# 08_-_POWER_CONTROL_AND_DISTRIBUTION.net
KiCad netlist of a schematic drawn in Altium Designer
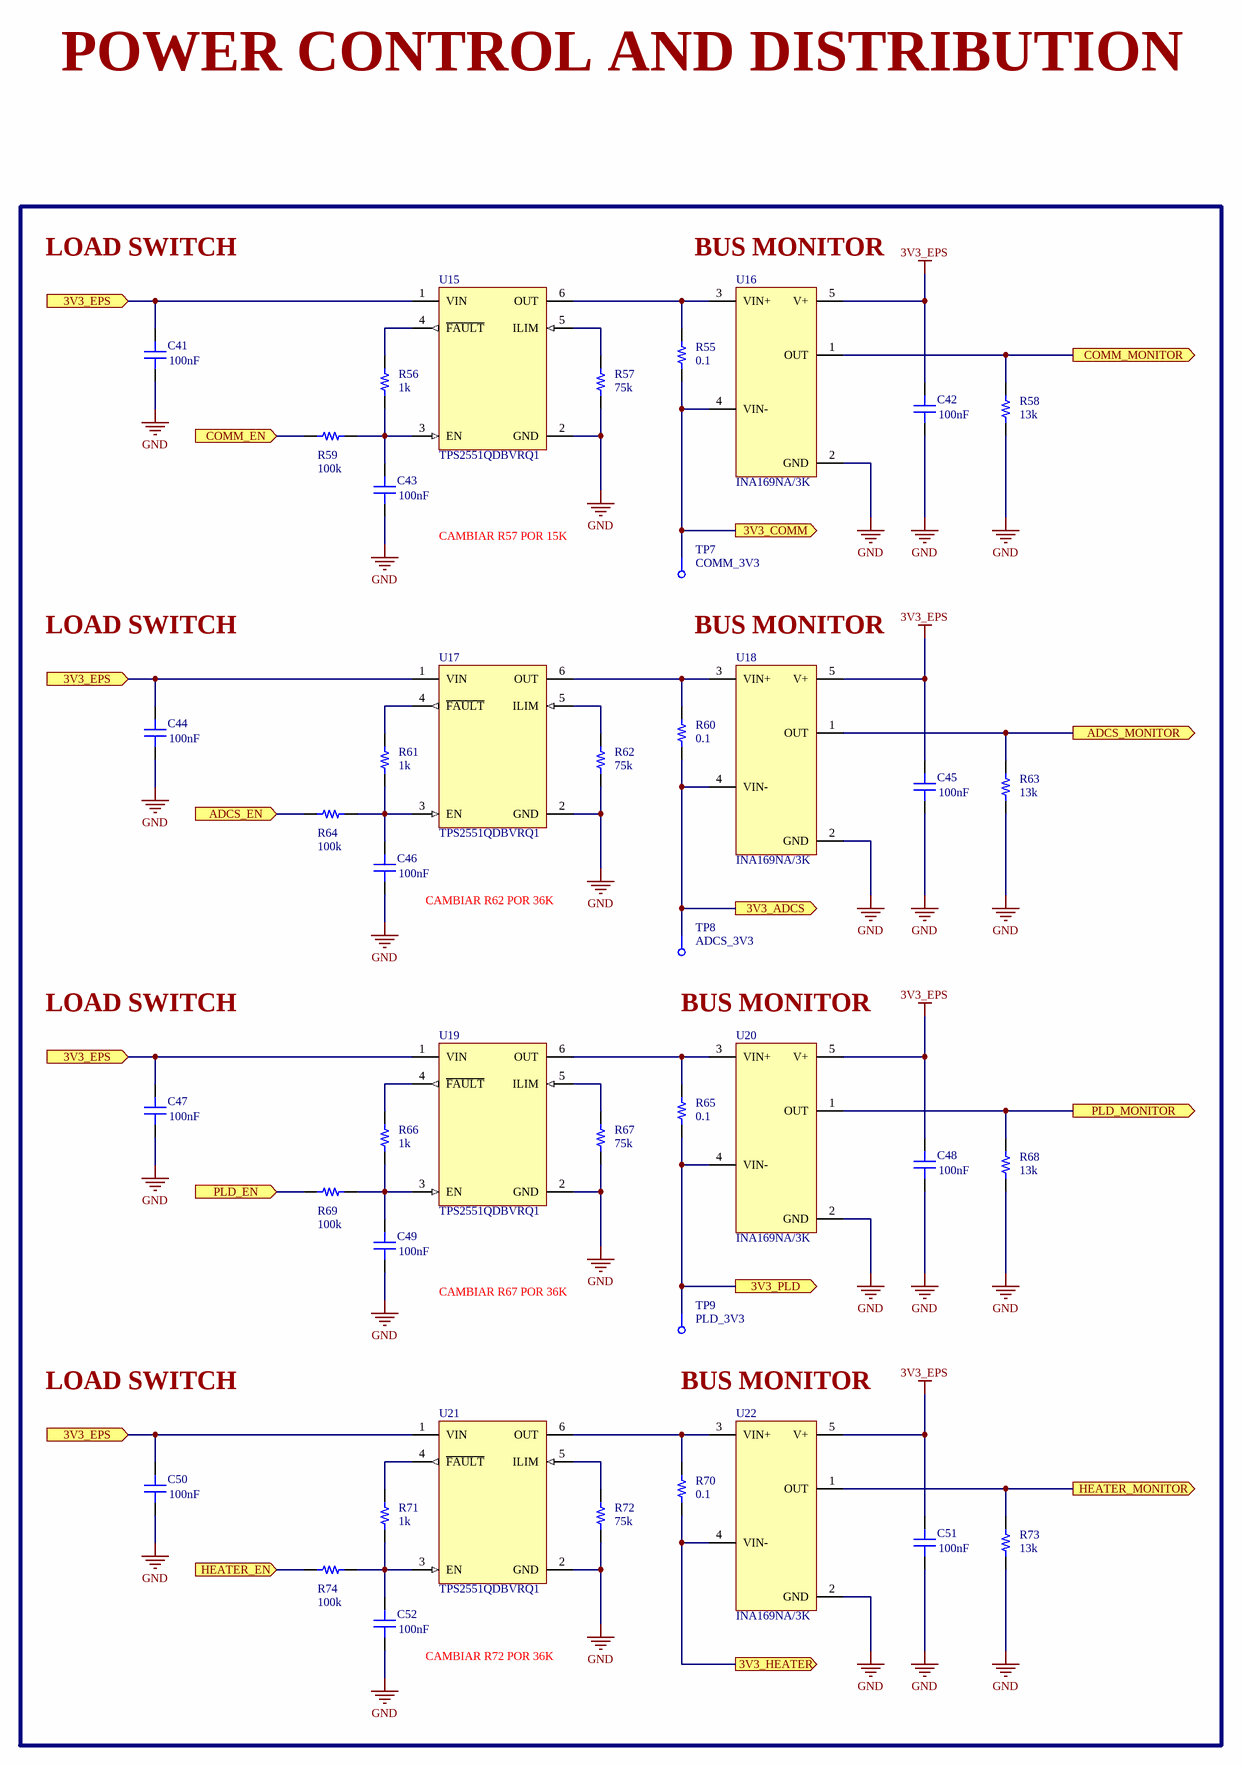
[diagram p0: [08] - POWER CONTROL AND DISTRIBUTION.SchDoc]

(export (version "E")
  (design (tool "Eeschema 10.0.6"))
  (components
    (comp (ref "C41")
      (value "C0603C104K8RACTU")
      (footprint "CAP 0603/1608")
      (description "CAP CER 0.1UF 10V X7R 0603")
      (fields
        (field (name "MANUFACTURER") "KEMET")
        (field (name "CAPACITANCE") "100nF")
        (field (name "TOLERANCE") "10%")
      )
      (libsource (lib "UVG") (part "C0603C104K8RACTU"))
    )
    (comp (ref "C42")
      (value "C0603C104K8RACTU")
      (footprint "CAP 0603/1608")
      (description "CAP CER 0.1UF 10V X7R 0603")
      (fields
        (field (name "MANUFACTURER") "KEMET")
        (field (name "CAPACITANCE") "100nF")
        (field (name "TOLERANCE") "10%")
      )
      (libsource (lib "UVG") (part "C0603C104K8RACTU"))
    )
    (comp (ref "C43")
      (value "C0603C104K8RACTU")
      (footprint "CAP 0603/1608")
      (description "CAP CER 0.1UF 10V X7R 0603")
      (fields
        (field (name "MANUFACTURER") "KEMET")
        (field (name "CAPACITANCE") "100nF")
        (field (name "TOLERANCE") "10%")
      )
      (libsource (lib "UVG") (part "C0603C104K8RACTU"))
    )
    (comp (ref "C44")
      (value "C0603C104K8RACTU")
      (footprint "CAP 0603/1608")
      (description "CAP CER 0.1UF 10V X7R 0603")
      (fields
        (field (name "MANUFACTURER") "KEMET")
        (field (name "CAPACITANCE") "100nF")
        (field (name "TOLERANCE") "10%")
      )
      (libsource (lib "UVG") (part "C0603C104K8RACTU"))
    )
    (comp (ref "C45")
      (value "C0603C104K8RACTU")
      (footprint "CAP 0603/1608")
      (description "CAP CER 0.1UF 10V X7R 0603")
      (fields
        (field (name "MANUFACTURER") "KEMET")
        (field (name "CAPACITANCE") "100nF")
        (field (name "TOLERANCE") "10%")
      )
      (libsource (lib "UVG") (part "C0603C104K8RACTU"))
    )
    (comp (ref "C46")
      (value "C0603C104K8RACTU")
      (footprint "CAP 0603/1608")
      (description "CAP CER 0.1UF 10V X7R 0603")
      (fields
        (field (name "MANUFACTURER") "KEMET")
        (field (name "CAPACITANCE") "100nF")
        (field (name "TOLERANCE") "10%")
      )
      (libsource (lib "UVG") (part "C0603C104K8RACTU"))
    )
    (comp (ref "C47")
      (value "C0603C104K8RACTU")
      (footprint "CAP 0603/1608")
      (description "CAP CER 0.1UF 10V X7R 0603")
      (fields
        (field (name "MANUFACTURER") "KEMET")
        (field (name "CAPACITANCE") "100nF")
        (field (name "TOLERANCE") "10%")
      )
      (libsource (lib "UVG") (part "C0603C104K8RACTU"))
    )
    (comp (ref "C48")
      (value "C0603C104K8RACTU")
      (footprint "CAP 0603/1608")
      (description "CAP CER 0.1UF 10V X7R 0603")
      (fields
        (field (name "MANUFACTURER") "KEMET")
        (field (name "CAPACITANCE") "100nF")
        (field (name "TOLERANCE") "10%")
      )
      (libsource (lib "UVG") (part "C0603C104K8RACTU"))
    )
    (comp (ref "C49")
      (value "C0603C104K8RACTU")
      (footprint "CAP 0603/1608")
      (description "CAP CER 0.1UF 10V X7R 0603")
      (fields
        (field (name "MANUFACTURER") "KEMET")
        (field (name "CAPACITANCE") "100nF")
        (field (name "TOLERANCE") "10%")
      )
      (libsource (lib "UVG") (part "C0603C104K8RACTU"))
    )
    (comp (ref "C50")
      (value "C0603C104K8RACTU")
      (footprint "CAP 0603/1608")
      (description "CAP CER 0.1UF 10V X7R 0603")
      (fields
        (field (name "MANUFACTURER") "KEMET")
        (field (name "CAPACITANCE") "100nF")
        (field (name "TOLERANCE") "10%")
      )
      (libsource (lib "UVG") (part "C0603C104K8RACTU"))
    )
    (comp (ref "C51")
      (value "C0603C104K8RACTU")
      (footprint "CAP 0603/1608")
      (description "CAP CER 0.1UF 10V X7R 0603")
      (fields
        (field (name "MANUFACTURER") "KEMET")
        (field (name "CAPACITANCE") "100nF")
        (field (name "TOLERANCE") "10%")
      )
      (libsource (lib "UVG") (part "C0603C104K8RACTU"))
    )
    (comp (ref "C52")
      (value "C0603C104K8RACTU")
      (footprint "CAP 0603/1608")
      (description "CAP CER 0.1UF 10V X7R 0603")
      (fields
        (field (name "MANUFACTURER") "KEMET")
        (field (name "CAPACITANCE") "100nF")
        (field (name "TOLERANCE") "10%")
      )
      (libsource (lib "UVG") (part "C0603C104K8RACTU"))
    )
    (comp (ref "R55")
      (value "RU1608FR100CS")
      (footprint "RES 0603/1608")
      (description "RES SMD 0.1 OHM 1% 1/4W 0603")
      (fields
        (field (name "MANUFACTURER") "Samsung")
        (field (name "RESISTANCE") "0.1")
        (field (name "TOLERANCE") "1%")
      )
      (libsource (lib "UVG") (part "RU1608FR100CS"))
    )
    (comp (ref "R56")
      (value "ESR03EZPJ102")
      (footprint "RES 0603/1608")
      (description "RES SMD 1K OHM 5% 1/4W 0603")
      (fields
        (field (name "MANUFACTURER") "Rohm")
        (field (name "RESISTANCE") "1k")
        (field (name "TOLERANCE") "5%")
      )
      (libsource (lib "UVG") (part "ESR03EZPJ102"))
    )
    (comp (ref "R57")
      (value "ERJ3EKF7502V")
      (footprint "RES 0603/1608")
      (description "RES SMD 75K OHM 1% 1/10W 0603")
      (fields
        (field (name "MANUFACTURER") "Panasonic")
        (field (name "RESISTANCE") "75k")
        (field (name "TOLERANCE") "1%")
      )
      (libsource (lib "UVG") (part "ERJ3EKF7502V"))
    )
    (comp (ref "R58")
      (value "RC0603JR-0713KL")
      (footprint "RES 0603/1608")
      (description "RES SMD 13K OHM 5% 1/10W 0603")
      (fields
        (field (name "MANUFACTURER") "Yageo")
        (field (name "RESISTANCE") "13k")
        (field (name "TOLERANCE") "5%")
      )
      (libsource (lib "UVG") (part "RC0603JR-0713KL"))
    )
    (comp (ref "R59")
      (value "CR0603-JW-104ELF")
      (footprint "RES 0603/1608")
      (description "RES SMD 100K OHM 5% 1/10W 0603")
      (fields
        (field (name "MANUFACTURER") "Bourns")
        (field (name "RESISTANCE") "100k")
        (field (name "TOLERANCE") "5%")
      )
      (libsource (lib "UVG") (part "CR0603-JW-104ELF"))
    )
    (comp (ref "R60")
      (value "RU1608FR100CS")
      (footprint "RES 0603/1608")
      (description "RES SMD 0.1 OHM 1% 1/4W 0603")
      (fields
        (field (name "MANUFACTURER") "Samsung")
        (field (name "RESISTANCE") "0.1")
        (field (name "TOLERANCE") "1%")
      )
      (libsource (lib "UVG") (part "RU1608FR100CS"))
    )
    (comp (ref "R61")
      (value "ESR03EZPJ102")
      (footprint "RES 0603/1608")
      (description "RES SMD 1K OHM 5% 1/4W 0603")
      (fields
        (field (name "MANUFACTURER") "Rohm")
        (field (name "RESISTANCE") "1k")
        (field (name "TOLERANCE") "5%")
      )
      (libsource (lib "UVG") (part "ESR03EZPJ102"))
    )
    (comp (ref "R62")
      (value "ERJ3EKF7502V")
      (footprint "RES 0603/1608")
      (description "RES SMD 75K OHM 1% 1/10W 0603")
      (fields
        (field (name "MANUFACTURER") "Panasonic")
        (field (name "RESISTANCE") "75k")
        (field (name "TOLERANCE") "1%")
      )
      (libsource (lib "UVG") (part "ERJ3EKF7502V"))
    )
    (comp (ref "R63")
      (value "RC0603JR-0713KL")
      (footprint "RES 0603/1608")
      (description "RES SMD 13K OHM 5% 1/10W 0603")
      (fields
        (field (name "MANUFACTURER") "Yageo")
        (field (name "RESISTANCE") "13k")
        (field (name "TOLERANCE") "5%")
      )
      (libsource (lib "UVG") (part "RC0603JR-0713KL"))
    )
    (comp (ref "R64")
      (value "CR0603-JW-104ELF")
      (footprint "RES 0603/1608")
      (description "RES SMD 100K OHM 5% 1/10W 0603")
      (fields
        (field (name "MANUFACTURER") "Bourns")
        (field (name "RESISTANCE") "100k")
        (field (name "TOLERANCE") "5%")
      )
      (libsource (lib "UVG") (part "CR0603-JW-104ELF"))
    )
    (comp (ref "R65")
      (value "RU1608FR100CS")
      (footprint "RES 0603/1608")
      (description "RES SMD 0.1 OHM 1% 1/4W 0603")
      (fields
        (field (name "MANUFACTURER") "Samsung")
        (field (name "RESISTANCE") "0.1")
        (field (name "TOLERANCE") "1%")
      )
      (libsource (lib "UVG") (part "RU1608FR100CS"))
    )
    (comp (ref "R66")
      (value "ESR03EZPJ102")
      (footprint "RES 0603/1608")
      (description "RES SMD 1K OHM 5% 1/4W 0603")
      (fields
        (field (name "MANUFACTURER") "Rohm")
        (field (name "RESISTANCE") "1k")
        (field (name "TOLERANCE") "5%")
      )
      (libsource (lib "UVG") (part "ESR03EZPJ102"))
    )
    (comp (ref "R67")
      (value "ERJ3EKF7502V")
      (footprint "RES 0603/1608")
      (description "RES SMD 75K OHM 1% 1/10W 0603")
      (fields
        (field (name "MANUFACTURER") "Panasonic")
        (field (name "RESISTANCE") "75k")
        (field (name "TOLERANCE") "1%")
      )
      (libsource (lib "UVG") (part "ERJ3EKF7502V"))
    )
    (comp (ref "R68")
      (value "RC0603JR-0713KL")
      (footprint "RES 0603/1608")
      (description "RES SMD 13K OHM 5% 1/10W 0603")
      (fields
        (field (name "MANUFACTURER") "Yageo")
        (field (name "RESISTANCE") "13k")
        (field (name "TOLERANCE") "5%")
      )
      (libsource (lib "UVG") (part "RC0603JR-0713KL"))
    )
    (comp (ref "R69")
      (value "CR0603-JW-104ELF")
      (footprint "RES 0603/1608")
      (description "RES SMD 100K OHM 5% 1/10W 0603")
      (fields
        (field (name "MANUFACTURER") "Bourns")
        (field (name "RESISTANCE") "100k")
        (field (name "TOLERANCE") "5%")
      )
      (libsource (lib "UVG") (part "CR0603-JW-104ELF"))
    )
    (comp (ref "R70")
      (value "RU1608FR100CS")
      (footprint "RES 0603/1608")
      (description "RES SMD 0.1 OHM 1% 1/4W 0603")
      (fields
        (field (name "MANUFACTURER") "Samsung")
        (field (name "RESISTANCE") "0.1")
        (field (name "TOLERANCE") "1%")
      )
      (libsource (lib "UVG") (part "RU1608FR100CS"))
    )
    (comp (ref "R71")
      (value "ESR03EZPJ102")
      (footprint "RES 0603/1608")
      (description "RES SMD 1K OHM 5% 1/4W 0603")
      (fields
        (field (name "MANUFACTURER") "Rohm")
        (field (name "RESISTANCE") "1k")
        (field (name "TOLERANCE") "5%")
      )
      (libsource (lib "UVG") (part "ESR03EZPJ102"))
    )
    (comp (ref "R72")
      (value "ERJ3EKF7502V")
      (footprint "RES 0603/1608")
      (description "RES SMD 75K OHM 1% 1/10W 0603")
      (fields
        (field (name "MANUFACTURER") "Panasonic")
        (field (name "RESISTANCE") "75k")
        (field (name "TOLERANCE") "1%")
      )
      (libsource (lib "UVG") (part "ERJ3EKF7502V"))
    )
    (comp (ref "R73")
      (value "RC0603JR-0713KL")
      (footprint "RES 0603/1608")
      (description "RES SMD 13K OHM 5% 1/10W 0603")
      (fields
        (field (name "MANUFACTURER") "Yageo")
        (field (name "RESISTANCE") "13k")
        (field (name "TOLERANCE") "5%")
      )
      (libsource (lib "UVG") (part "RC0603JR-0713KL"))
    )
    (comp (ref "R74")
      (value "CR0603-JW-104ELF")
      (footprint "RES 0603/1608")
      (description "RES SMD 100K OHM 5% 1/10W 0603")
      (fields
        (field (name "MANUFACTURER") "Bourns")
        (field (name "RESISTANCE") "100k")
        (field (name "TOLERANCE") "5%")
      )
      (libsource (lib "UVG") (part "CR0603-JW-104ELF"))
    )
    (comp (ref "TP7")
      (value "COMM_3V3")
      (footprint "Testpoint")
      (description "GENERIC TESTPOINT")
      (libsource (lib "UVG") (part "TESTPOINT"))
    )
    (comp (ref "TP8")
      (value "ADCS_3V3")
      (footprint "Testpoint")
      (description "GENERIC TESTPOINT")
      (libsource (lib "UVG") (part "TESTPOINT"))
    )
    (comp (ref "TP9")
      (value "PLD_3V3")
      (footprint "Testpoint")
      (description "GENERIC TESTPOINT")
      (libsource (lib "UVG") (part "TESTPOINT"))
    )
    (comp (ref "U15")
      (value "TPS2551QDBVRQ1")
      (footprint "SOT23-6")
      (description "IC POWER-DIST SWITCH ADJ SOT23-6")
      (fields (field (name "MANUFACTURER") "Texas Instruments"))
      (libsource (lib "UVG") (part "TPS2551QDBVRQ1"))
    )
    (comp (ref "U16")
      (value "INA169NA/3K")
      (footprint "SOT95P245X110-5N")
      (description "IC CURRENT MONITOR 0.5% SOT23-5")
      (fields (field (name "MANUFACTURER") "Texas Instruments"))
      (libsource (lib "UVG") (part "INA169NA/3K"))
    )
    (comp (ref "U17")
      (value "TPS2551QDBVRQ1")
      (footprint "SOT23-6")
      (description "IC POWER-DIST SWITCH ADJ SOT23-6")
      (fields (field (name "MANUFACTURER") "Texas Instruments"))
      (libsource (lib "UVG") (part "TPS2551QDBVRQ1"))
    )
    (comp (ref "U18")
      (value "INA169NA/3K")
      (footprint "SOT95P245X110-5N")
      (description "IC CURRENT MONITOR 0.5% SOT23-5")
      (fields (field (name "MANUFACTURER") "Texas Instruments"))
      (libsource (lib "UVG") (part "INA169NA/3K"))
    )
    (comp (ref "U19")
      (value "TPS2551QDBVRQ1")
      (footprint "SOT23-6")
      (description "IC POWER-DIST SWITCH ADJ SOT23-6")
      (fields (field (name "MANUFACTURER") "Texas Instruments"))
      (libsource (lib "UVG") (part "TPS2551QDBVRQ1"))
    )
    (comp (ref "U20")
      (value "INA169NA/3K")
      (footprint "SOT95P245X110-5N")
      (description "IC CURRENT MONITOR 0.5% SOT23-5")
      (fields (field (name "MANUFACTURER") "Texas Instruments"))
      (libsource (lib "UVG") (part "INA169NA/3K"))
    )
    (comp (ref "U21")
      (value "TPS2551QDBVRQ1")
      (footprint "SOT23-6")
      (description "IC POWER-DIST SWITCH ADJ SOT23-6")
      (fields (field (name "MANUFACTURER") "Texas Instruments"))
      (libsource (lib "UVG") (part "TPS2551QDBVRQ1"))
    )
    (comp (ref "U22")
      (value "INA169NA/3K")
      (footprint "SOT95P245X110-5N")
      (description "IC CURRENT MONITOR 0.5% SOT23-5")
      (fields (field (name "MANUFACTURER") "Texas Instruments"))
      (libsource (lib "UVG") (part "INA169NA/3K"))
    )
  )
  (nets
    (net (code "1") (name "/3V3_ADCS") (class "Default")
      (node (ref "R60") (pin "2") (pinfunction "2_2") (pintype "passive"))
      (node (ref "TP8") (pin "1") (pinfunction "1_1") (pintype "passive"))
      (node (ref "U18") (pin "4") (pinfunction "VIN-_4") (pintype "power_in"))
    )
    (net (code "2") (name "/3V3_COMM") (class "Default")
      (node (ref "R55") (pin "2") (pinfunction "2_2") (pintype "passive"))
      (node (ref "TP7") (pin "1") (pinfunction "1_1") (pintype "passive"))
      (node (ref "U16") (pin "4") (pinfunction "VIN-_4") (pintype "power_in"))
    )
    (net (code "3") (name "/3V3_HEATER") (class "Default")
      (node (ref "R70") (pin "2") (pinfunction "2_2") (pintype "passive"))
      (node (ref "U22") (pin "4") (pinfunction "VIN-_4") (pintype "power_in"))
    )
    (net (code "4") (name "/3V3_PLD") (class "Default")
      (node (ref "R65") (pin "2") (pinfunction "2_2") (pintype "passive"))
      (node (ref "TP9") (pin "1") (pinfunction "1_1") (pintype "passive"))
      (node (ref "U20") (pin "4") (pinfunction "VIN-_4") (pintype "power_in"))
    )
    (net (code "5") (name "/ADCS_EN") (class "Default")
      (node (ref "R64") (pin "1") (pinfunction "1_1") (pintype "passive"))
    )
    (net (code "6") (name "/ADCS_MONITOR") (class "Default")
      (node (ref "R63") (pin "2") (pinfunction "2_2") (pintype "passive"))
      (node (ref "U18") (pin "1") (pinfunction "OUT_1") (pintype "power_in"))
    )
    (net (code "7") (name "/COMM_EN") (class "Default")
      (node (ref "R59") (pin "1") (pinfunction "1_1") (pintype "passive"))
    )
    (net (code "8") (name "/COMM_MONITOR") (class "Default")
      (node (ref "R58") (pin "2") (pinfunction "2_2") (pintype "passive"))
      (node (ref "U16") (pin "1") (pinfunction "OUT_1") (pintype "power_in"))
    )
    (net (code "9") (name "/HEATER_EN") (class "Default")
      (node (ref "R74") (pin "1") (pinfunction "1_1") (pintype "passive"))
    )
    (net (code "10") (name "/HEATER_MONITOR") (class "Default")
      (node (ref "R73") (pin "2") (pinfunction "2_2") (pintype "passive"))
      (node (ref "U22") (pin "1") (pinfunction "OUT_1") (pintype "power_in"))
    )
    (net (code "11") (name "/PLD_EN") (class "Default")
      (node (ref "R69") (pin "1") (pinfunction "1_1") (pintype "passive"))
    )
    (net (code "12") (name "/PLD_MONITOR") (class "Default")
      (node (ref "R68") (pin "2") (pinfunction "2_2") (pintype "passive"))
      (node (ref "U20") (pin "1") (pinfunction "OUT_1") (pintype "power_in"))
    )
    (net (code "13") (name "3V3_EPS") (class "Default")
      (node (ref "C41") (pin "2") (pinfunction "2_2") (pintype "passive"))
      (node (ref "C42") (pin "2") (pinfunction "2_2") (pintype "passive"))
      (node (ref "C44") (pin "2") (pinfunction "2_2") (pintype "passive"))
      (node (ref "C45") (pin "2") (pinfunction "2_2") (pintype "passive"))
      (node (ref "C47") (pin "2") (pinfunction "2_2") (pintype "passive"))
      (node (ref "C48") (pin "2") (pinfunction "2_2") (pintype "passive"))
      (node (ref "C50") (pin "2") (pinfunction "2_2") (pintype "passive"))
      (node (ref "C51") (pin "2") (pinfunction "2_2") (pintype "passive"))
      (node (ref "U15") (pin "1") (pinfunction "VIN_1") (pintype "power_in"))
      (node (ref "U16") (pin "5") (pinfunction "V+_5") (pintype "passive"))
      (node (ref "U17") (pin "1") (pinfunction "VIN_1") (pintype "power_in"))
      (node (ref "U18") (pin "5") (pinfunction "V+_5") (pintype "passive"))
      (node (ref "U19") (pin "1") (pinfunction "VIN_1") (pintype "power_in"))
      (node (ref "U20") (pin "5") (pinfunction "V+_5") (pintype "passive"))
      (node (ref "U21") (pin "1") (pinfunction "VIN_1") (pintype "power_in"))
      (node (ref "U22") (pin "5") (pinfunction "V+_5") (pintype "passive"))
    )
    (net (code "14") (name "GND") (class "Default")
      (node (ref "C41") (pin "1") (pinfunction "1_1") (pintype "passive"))
      (node (ref "C42") (pin "1") (pinfunction "1_1") (pintype "passive"))
      (node (ref "C43") (pin "1") (pinfunction "1_1") (pintype "passive"))
      (node (ref "C44") (pin "1") (pinfunction "1_1") (pintype "passive"))
      (node (ref "C45") (pin "1") (pinfunction "1_1") (pintype "passive"))
      (node (ref "C46") (pin "1") (pinfunction "1_1") (pintype "passive"))
      (node (ref "C47") (pin "1") (pinfunction "1_1") (pintype "passive"))
      (node (ref "C48") (pin "1") (pinfunction "1_1") (pintype "passive"))
      (node (ref "C49") (pin "1") (pinfunction "1_1") (pintype "passive"))
      (node (ref "C50") (pin "1") (pinfunction "1_1") (pintype "passive"))
      (node (ref "C51") (pin "1") (pinfunction "1_1") (pintype "passive"))
      (node (ref "C52") (pin "1") (pinfunction "1_1") (pintype "passive"))
      (node (ref "R57") (pin "1") (pinfunction "1_1") (pintype "passive"))
      (node (ref "R58") (pin "1") (pinfunction "1_1") (pintype "passive"))
      (node (ref "R62") (pin "1") (pinfunction "1_1") (pintype "passive"))
      (node (ref "R63") (pin "1") (pinfunction "1_1") (pintype "passive"))
      (node (ref "R67") (pin "1") (pinfunction "1_1") (pintype "passive"))
      (node (ref "R68") (pin "1") (pinfunction "1_1") (pintype "passive"))
      (node (ref "R72") (pin "1") (pinfunction "1_1") (pintype "passive"))
      (node (ref "R73") (pin "1") (pinfunction "1_1") (pintype "passive"))
      (node (ref "U15") (pin "2") (pinfunction "GND_2") (pintype "power_in"))
      (node (ref "U16") (pin "2") (pinfunction "GND_2") (pintype "power_in"))
      (node (ref "U17") (pin "2") (pinfunction "GND_2") (pintype "power_in"))
      (node (ref "U18") (pin "2") (pinfunction "GND_2") (pintype "power_in"))
      (node (ref "U19") (pin "2") (pinfunction "GND_2") (pintype "power_in"))
      (node (ref "U20") (pin "2") (pinfunction "GND_2") (pintype "power_in"))
      (node (ref "U21") (pin "2") (pinfunction "GND_2") (pintype "power_in"))
      (node (ref "U22") (pin "2") (pinfunction "GND_2") (pintype "power_in"))
    )
    (net (code "15") (name "Net-(U15-EN)") (class "Default")
      (node (ref "C43") (pin "2") (pinfunction "2_2") (pintype "passive"))
      (node (ref "R56") (pin "1") (pinfunction "1_1") (pintype "passive"))
      (node (ref "R59") (pin "2") (pinfunction "2_2") (pintype "passive"))
      (node (ref "U15") (pin "3") (pinfunction "EN_3") (pintype "input"))
    )
    (net (code "16") (name "Net-(U15-ILIM)") (class "Default")
      (node (ref "R57") (pin "2") (pinfunction "2_2") (pintype "passive"))
      (node (ref "U15") (pin "5") (pinfunction "ILIM_5") (pintype "input"))
    )
    (net (code "17") (name "Net-(U15-OUT)") (class "Default")
      (node (ref "R55") (pin "1") (pinfunction "1_1") (pintype "passive"))
      (node (ref "U15") (pin "6") (pinfunction "OUT_6") (pintype "power_in"))
      (node (ref "U16") (pin "3") (pinfunction "VIN+_3") (pintype "power_in"))
    )
    (net (code "18") (name "Net-(U15-~{FAULT})") (class "Default")
      (node (ref "R56") (pin "2") (pinfunction "2_2") (pintype "passive"))
      (node (ref "U15") (pin "4") (pinfunction "~{FAULT}_4") (pintype "output"))
    )
    (net (code "19") (name "Net-(U17-EN)") (class "Default")
      (node (ref "C46") (pin "2") (pinfunction "2_2") (pintype "passive"))
      (node (ref "R61") (pin "1") (pinfunction "1_1") (pintype "passive"))
      (node (ref "R64") (pin "2") (pinfunction "2_2") (pintype "passive"))
      (node (ref "U17") (pin "3") (pinfunction "EN_3") (pintype "input"))
    )
    (net (code "20") (name "Net-(U17-ILIM)") (class "Default")
      (node (ref "R62") (pin "2") (pinfunction "2_2") (pintype "passive"))
      (node (ref "U17") (pin "5") (pinfunction "ILIM_5") (pintype "input"))
    )
    (net (code "21") (name "Net-(U17-OUT)") (class "Default")
      (node (ref "R60") (pin "1") (pinfunction "1_1") (pintype "passive"))
      (node (ref "U17") (pin "6") (pinfunction "OUT_6") (pintype "power_in"))
      (node (ref "U18") (pin "3") (pinfunction "VIN+_3") (pintype "power_in"))
    )
    (net (code "22") (name "Net-(U17-~{FAULT})") (class "Default")
      (node (ref "R61") (pin "2") (pinfunction "2_2") (pintype "passive"))
      (node (ref "U17") (pin "4") (pinfunction "~{FAULT}_4") (pintype "output"))
    )
    (net (code "23") (name "Net-(U19-EN)") (class "Default")
      (node (ref "C49") (pin "2") (pinfunction "2_2") (pintype "passive"))
      (node (ref "R66") (pin "1") (pinfunction "1_1") (pintype "passive"))
      (node (ref "R69") (pin "2") (pinfunction "2_2") (pintype "passive"))
      (node (ref "U19") (pin "3") (pinfunction "EN_3") (pintype "input"))
    )
    (net (code "24") (name "Net-(U19-ILIM)") (class "Default")
      (node (ref "R67") (pin "2") (pinfunction "2_2") (pintype "passive"))
      (node (ref "U19") (pin "5") (pinfunction "ILIM_5") (pintype "input"))
    )
    (net (code "25") (name "Net-(U19-OUT)") (class "Default")
      (node (ref "R65") (pin "1") (pinfunction "1_1") (pintype "passive"))
      (node (ref "U19") (pin "6") (pinfunction "OUT_6") (pintype "power_in"))
      (node (ref "U20") (pin "3") (pinfunction "VIN+_3") (pintype "power_in"))
    )
    (net (code "26") (name "Net-(U19-~{FAULT})") (class "Default")
      (node (ref "R66") (pin "2") (pinfunction "2_2") (pintype "passive"))
      (node (ref "U19") (pin "4") (pinfunction "~{FAULT}_4") (pintype "output"))
    )
    (net (code "27") (name "Net-(U21-EN)") (class "Default")
      (node (ref "C52") (pin "2") (pinfunction "2_2") (pintype "passive"))
      (node (ref "R71") (pin "1") (pinfunction "1_1") (pintype "passive"))
      (node (ref "R74") (pin "2") (pinfunction "2_2") (pintype "passive"))
      (node (ref "U21") (pin "3") (pinfunction "EN_3") (pintype "input"))
    )
    (net (code "28") (name "Net-(U21-ILIM)") (class "Default")
      (node (ref "R72") (pin "2") (pinfunction "2_2") (pintype "passive"))
      (node (ref "U21") (pin "5") (pinfunction "ILIM_5") (pintype "input"))
    )
    (net (code "29") (name "Net-(U21-OUT)") (class "Default")
      (node (ref "R70") (pin "1") (pinfunction "1_1") (pintype "passive"))
      (node (ref "U21") (pin "6") (pinfunction "OUT_6") (pintype "power_in"))
      (node (ref "U22") (pin "3") (pinfunction "VIN+_3") (pintype "power_in"))
    )
    (net (code "30") (name "Net-(U21-~{FAULT})") (class "Default")
      (node (ref "R71") (pin "2") (pinfunction "2_2") (pintype "passive"))
      (node (ref "U21") (pin "4") (pinfunction "~{FAULT}_4") (pintype "output"))
    )
  )
)
